# EngineCard.net
KiCad netlist of a schematic drawn in EAGLE
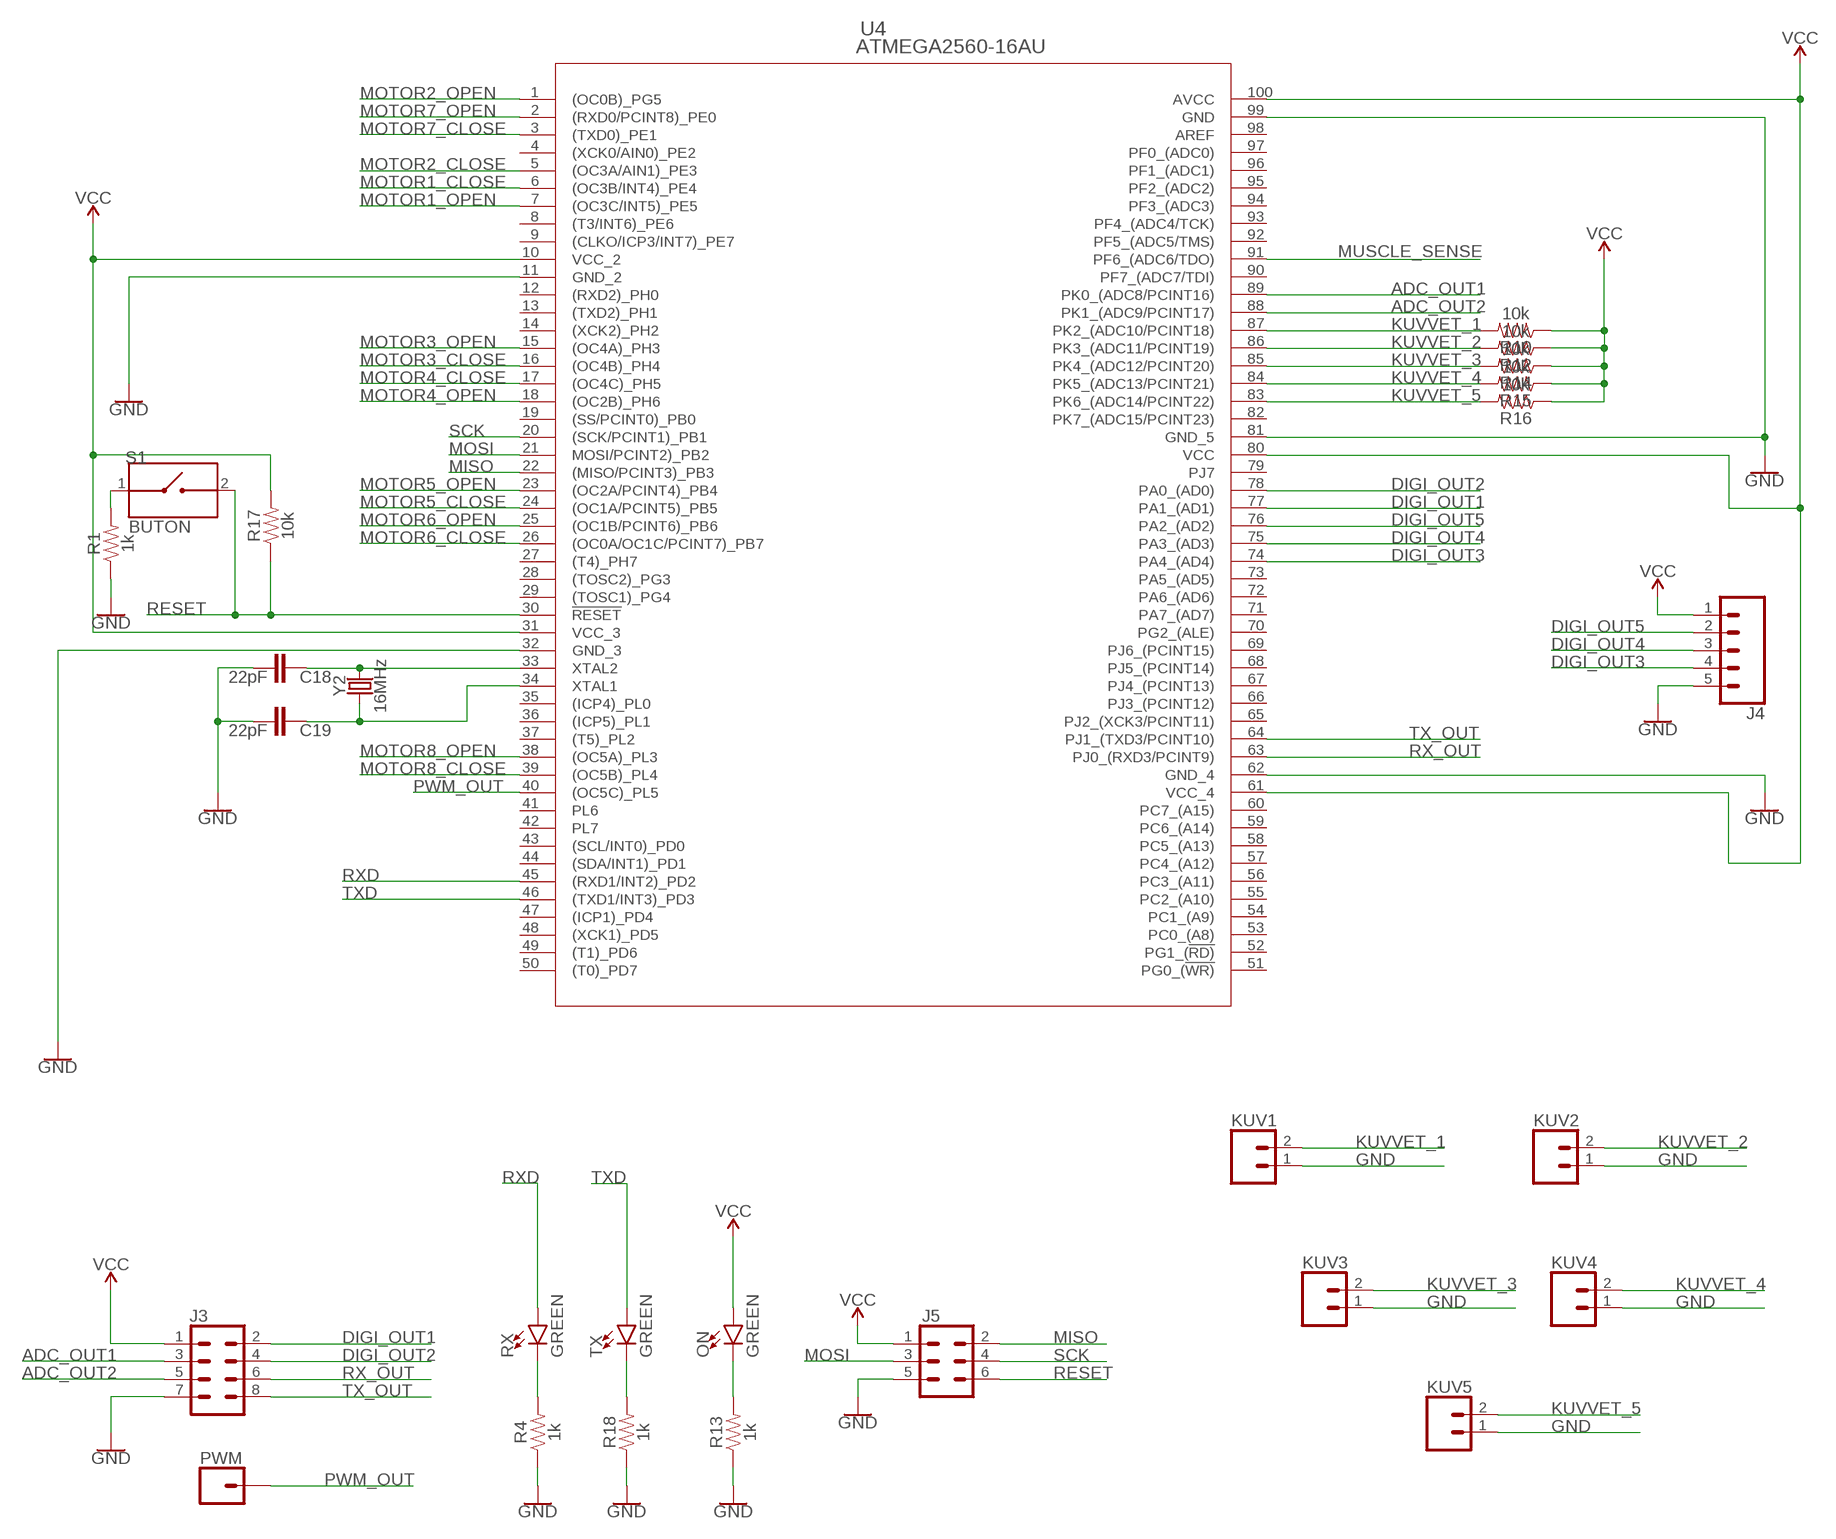
[diagram p0: schematic, sheet 1, part 1 of 2]
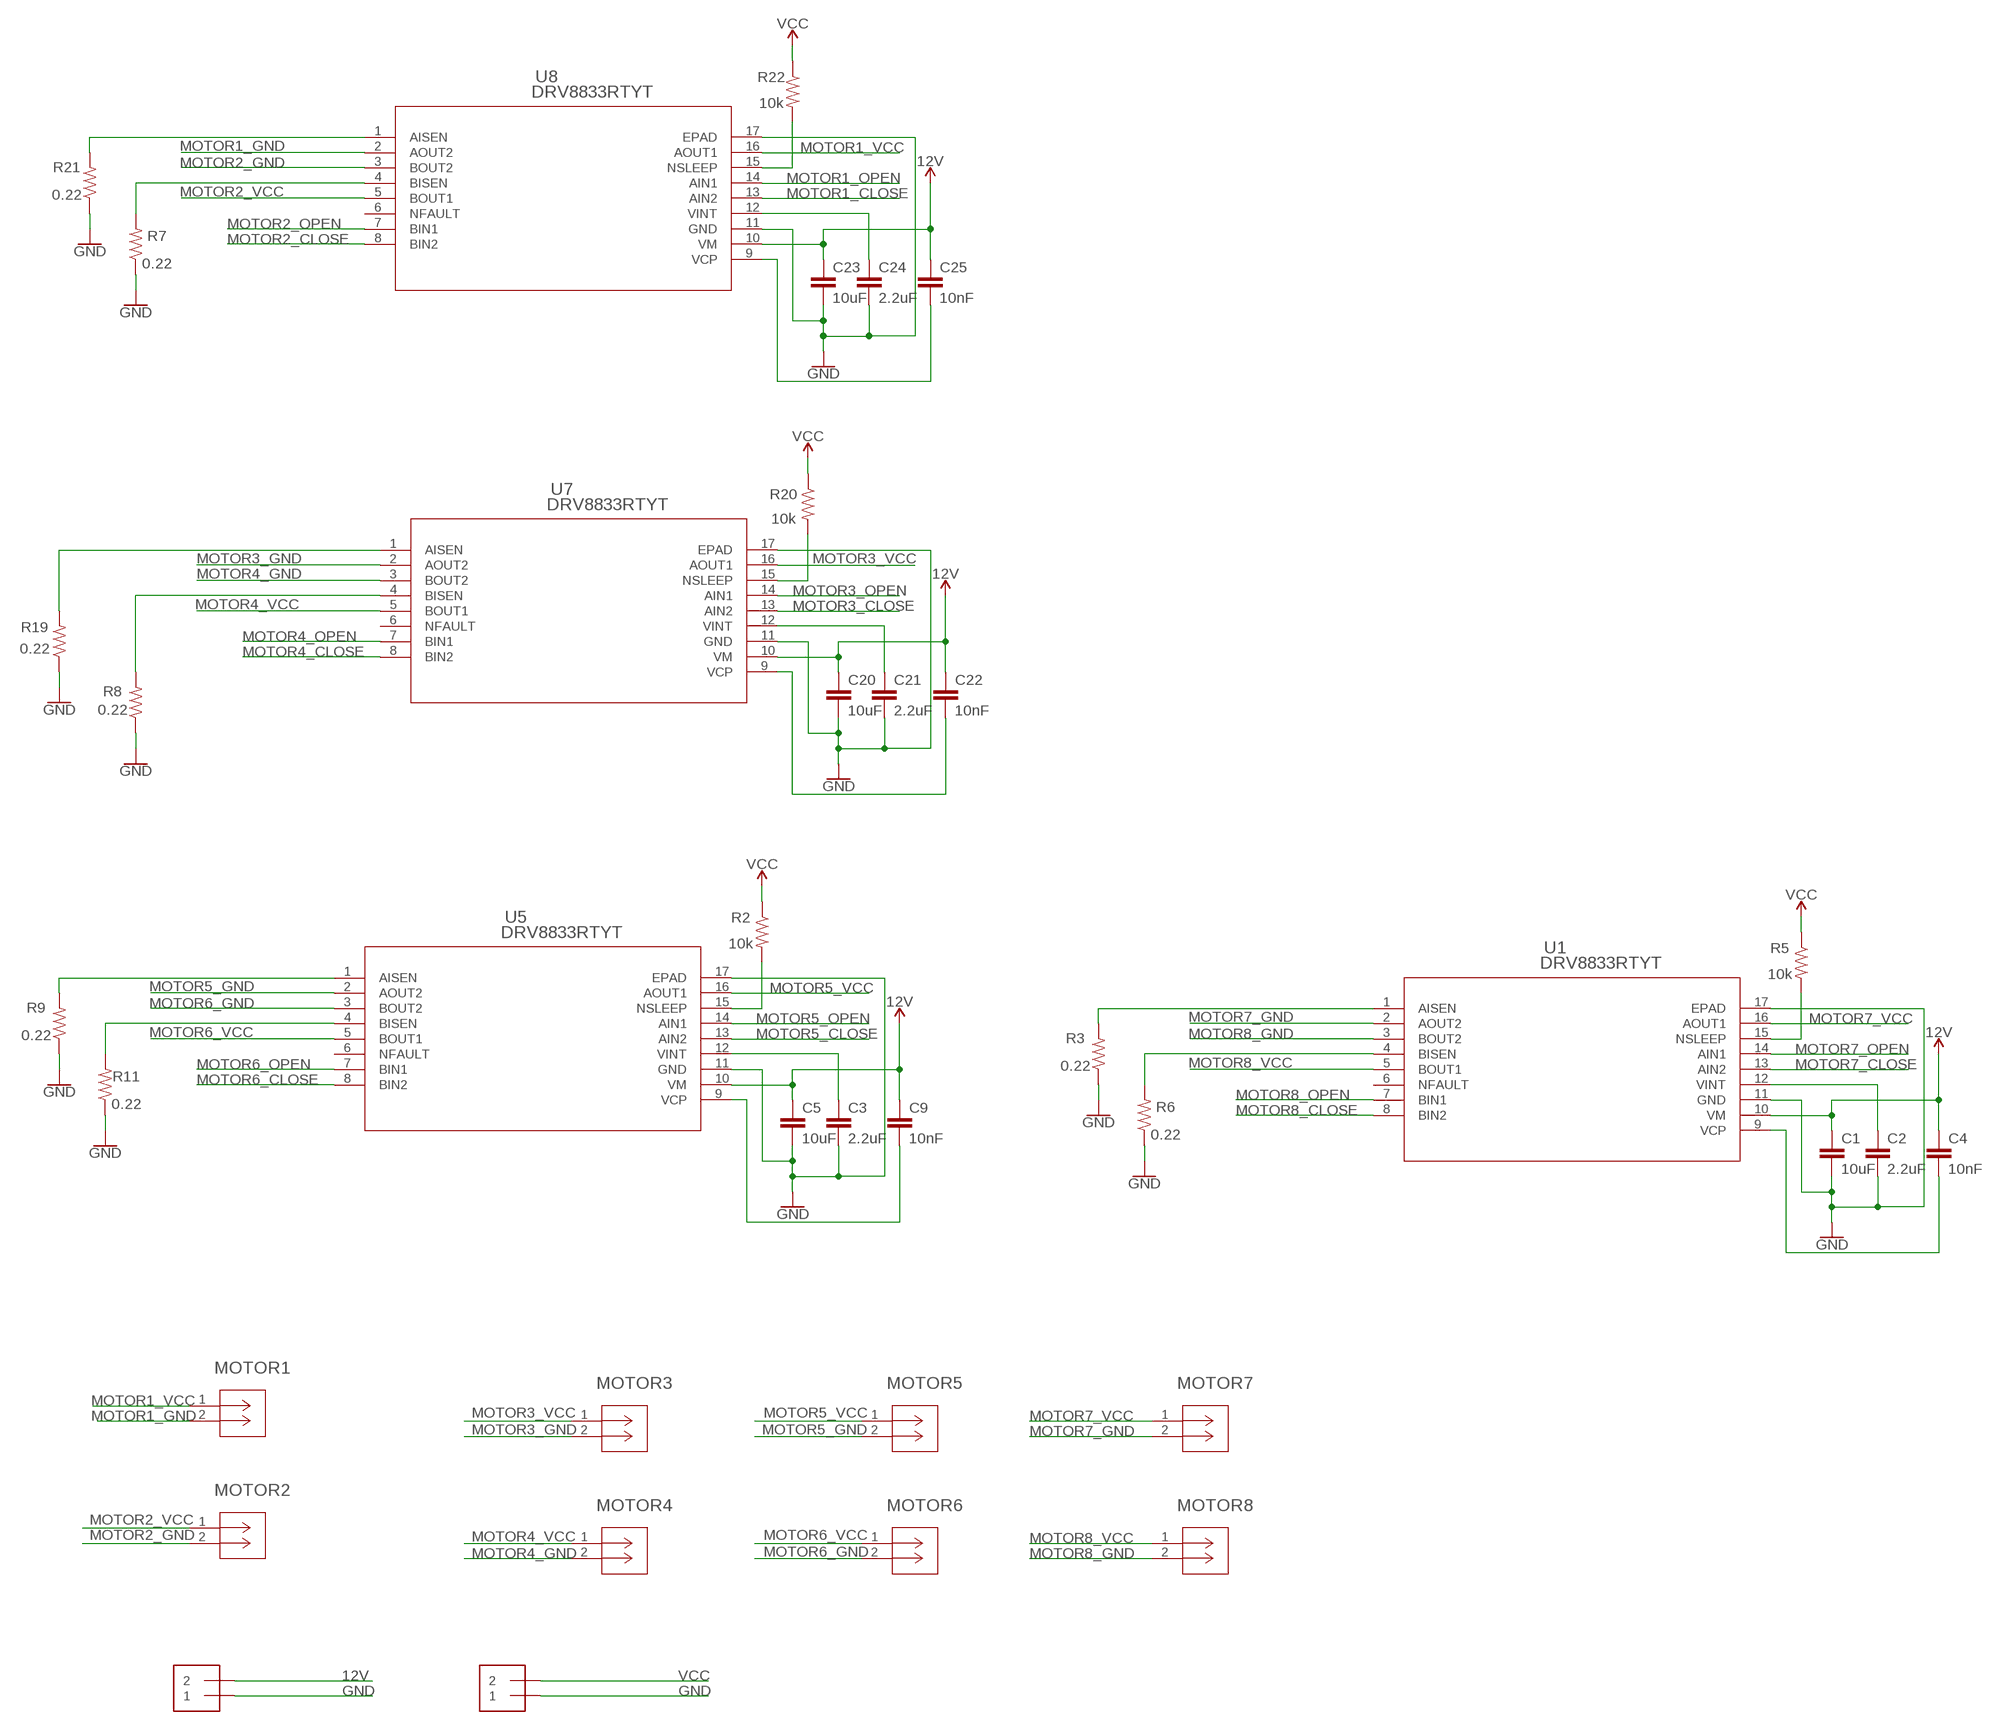
[diagram p1: schematic, sheet 1, part 2 of 2]

(export (version "E")
  (design (tool "Eeschema 10.0.6"))
  (components
    (comp (ref "C1")
      (value "10uF")
      (footprint "eagle-import:0603")
      (libsource (lib "eagle-import") (part "10UF-0603-6.3V-20%"))
    )
    (comp (ref "C2")
      (value "2.2uF")
      (footprint "eagle-import:0603")
      (libsource (lib "eagle-import") (part "2.2UF-0603-10V-20%"))
    )
    (comp (ref "C3")
      (value "2.2uF")
      (footprint "eagle-import:0603")
      (libsource (lib "eagle-import") (part "2.2UF-0603-10V-20%"))
    )
    (comp (ref "C4")
      (value "10nF")
      (footprint "eagle-import:0603")
      (libsource (lib "eagle-import") (part "10NF-0603-50V-10%"))
    )
    (comp (ref "C5")
      (value "10uF")
      (footprint "eagle-import:0603")
      (libsource (lib "eagle-import") (part "10UF-0603-6.3V-20%"))
    )
    (comp (ref "C9")
      (value "10nF")
      (footprint "eagle-import:0603")
      (libsource (lib "eagle-import") (part "10NF-0603-50V-10%"))
    )
    (comp (ref "C18")
      (value "22pF")
      (footprint "eagle-import:0603")
      (libsource (lib "eagle-import") (part "22PF-0603-50V-5%"))
    )
    (comp (ref "C19")
      (value "22pF")
      (footprint "eagle-import:0603")
      (libsource (lib "eagle-import") (part "22PF-0603-50V-5%"))
    )
    (comp (ref "C20")
      (value "10uF")
      (footprint "eagle-import:0603")
      (libsource (lib "eagle-import") (part "10UF-0603-6.3V-20%"))
    )
    (comp (ref "C21")
      (value "2.2uF")
      (footprint "eagle-import:0603")
      (libsource (lib "eagle-import") (part "2.2UF-0603-10V-20%"))
    )
    (comp (ref "C22")
      (value "10nF")
      (footprint "eagle-import:0603")
      (libsource (lib "eagle-import") (part "10NF-0603-50V-10%"))
    )
    (comp (ref "C23")
      (value "10uF")
      (footprint "eagle-import:0603")
      (libsource (lib "eagle-import") (part "10UF-0603-6.3V-20%"))
    )
    (comp (ref "C24")
      (value "2.2uF")
      (footprint "eagle-import:0603")
      (libsource (lib "eagle-import") (part "2.2UF-0603-10V-20%"))
    )
    (comp (ref "C25")
      (value "10nF")
      (footprint "eagle-import:0603")
      (libsource (lib "eagle-import") (part "10NF-0603-50V-10%"))
    )
    (comp (ref "J3")
      (value "CONN_04X2")
      (footprint "eagle-import:2X4")
      (libsource (lib "eagle-import") (part "CONN_04X2"))
    )
    (comp (ref "J4")
      (value "CONN_05NO_SILK")
      (footprint "eagle-import:1X05_NO_SILK")
      (libsource (lib "eagle-import") (part "CONN_05NO_SILK"))
    )
    (comp (ref "J5")
      (value "CONN_03X2NO_SILK")
      (footprint "eagle-import:2X3-NS")
      (libsource (lib "eagle-import") (part "CONN_03X2NO_SILK"))
    )
    (comp (ref "KUV1")
      (value "CONN_02")
      (footprint "eagle-import:1X02")
      (libsource (lib "eagle-import") (part "CONN_02"))
    )
    (comp (ref "KUV2")
      (value "CONN_02")
      (footprint "eagle-import:1X02")
      (libsource (lib "eagle-import") (part "CONN_02"))
    )
    (comp (ref "KUV3")
      (value "CONN_02")
      (footprint "eagle-import:1X02")
      (libsource (lib "eagle-import") (part "CONN_02"))
    )
    (comp (ref "KUV4")
      (value "CONN_02")
      (footprint "eagle-import:1X02")
      (libsource (lib "eagle-import") (part "CONN_02"))
    )
    (comp (ref "KUV5")
      (value "CONN_02")
      (footprint "eagle-import:1X02")
      (libsource (lib "eagle-import") (part "CONN_02"))
    )
    (comp (ref "MOTOR1")
      (value "530470210")
      (footprint "eagle-import:CON_530470210_MOL")
      (fields (field (name "COPYRIGHT") "Copyright (C) 2022 Ultra Librarian. All rights reserved."))
      (libsource (lib "eagle-import") (part "530470210"))
    )
    (comp (ref "MOTOR2")
      (value "530470210")
      (footprint "eagle-import:CON_530470210_MOL")
      (fields (field (name "COPYRIGHT") "Copyright (C) 2022 Ultra Librarian. All rights reserved."))
      (libsource (lib "eagle-import") (part "530470210"))
    )
    (comp (ref "MOTOR3")
      (value "530470210")
      (footprint "eagle-import:CON_530470210_MOL")
      (fields (field (name "COPYRIGHT") "Copyright (C) 2022 Ultra Librarian. All rights reserved."))
      (libsource (lib "eagle-import") (part "530470210"))
    )
    (comp (ref "MOTOR4")
      (value "530470210")
      (footprint "eagle-import:CON_530470210_MOL")
      (fields (field (name "COPYRIGHT") "Copyright (C) 2022 Ultra Librarian. All rights reserved."))
      (libsource (lib "eagle-import") (part "530470210"))
    )
    (comp (ref "MOTOR5")
      (value "530470210")
      (footprint "eagle-import:CON_530470210_MOL")
      (fields (field (name "COPYRIGHT") "Copyright (C) 2022 Ultra Librarian. All rights reserved."))
      (libsource (lib "eagle-import") (part "530470210"))
    )
    (comp (ref "MOTOR6")
      (value "530470210")
      (footprint "eagle-import:CON_530470210_MOL")
      (fields (field (name "COPYRIGHT") "Copyright (C) 2022 Ultra Librarian. All rights reserved."))
      (libsource (lib "eagle-import") (part "530470210"))
    )
    (comp (ref "MOTOR7")
      (value "530470210")
      (footprint "eagle-import:CON_530470210_MOL")
      (fields (field (name "COPYRIGHT") "Copyright (C) 2022 Ultra Librarian. All rights reserved."))
      (libsource (lib "eagle-import") (part "530470210"))
    )
    (comp (ref "MOTOR8")
      (value "530470210")
      (footprint "eagle-import:CON_530470210_MOL")
      (fields (field (name "COPYRIGHT") "Copyright (C) 2022 Ultra Librarian. All rights reserved."))
      (libsource (lib "eagle-import") (part "530470210"))
    )
    (comp (ref "ON")
      (value "GREEN")
      (footprint "eagle-import:LED-0603")
      (libsource (lib "eagle-import") (part "LED-GREEN0603"))
    )
    (comp (ref "PIL")
      (value "1X2-3.5MM")
      (footprint "eagle-import:1X2-3.5MM")
      (libsource (lib "eagle-import") (part "1X2-3.5MM"))
    )
    (comp (ref "PWM")
      (value "CONN_01")
      (footprint "eagle-import:1X01")
      (libsource (lib "eagle-import") (part "CONN_01"))
    )
    (comp (ref "R1")
      (value "1k")
      (footprint "eagle-import:0603")
      (libsource (lib "eagle-import") (part "10KOHM-0603-1/10W-1%"))
    )
    (comp (ref "R2")
      (value "10k")
      (footprint "eagle-import:0603")
      (libsource (lib "eagle-import") (part "10KOHM-0603-1/10W-1%"))
    )
    (comp (ref "R3")
      (value "0.22")
      (footprint "eagle-import:0805")
      (libsource (lib "eagle-import") (part "0.22OHM-0805-1/4W-1%"))
    )
    (comp (ref "R4")
      (value "1k")
      (footprint "eagle-import:0603")
      (libsource (lib "eagle-import") (part "1KOHM-0603-1/10W-1%"))
    )
    (comp (ref "R5")
      (value "10k")
      (footprint "eagle-import:0603")
      (libsource (lib "eagle-import") (part "10KOHM-0603-1/10W-1%"))
    )
    (comp (ref "R6")
      (value "0.22")
      (footprint "eagle-import:0805")
      (libsource (lib "eagle-import") (part "0.22OHM-0805-1/4W-1%"))
    )
    (comp (ref "R7")
      (value "0.22")
      (footprint "eagle-import:0805")
      (libsource (lib "eagle-import") (part "0.22OHM-0805-1/4W-1%"))
    )
    (comp (ref "R8")
      (value "0.22")
      (footprint "eagle-import:0805")
      (libsource (lib "eagle-import") (part "0.22OHM-0805-1/4W-1%"))
    )
    (comp (ref "R9")
      (value "0.22")
      (footprint "eagle-import:0805")
      (libsource (lib "eagle-import") (part "0.22OHM-0805-1/4W-1%"))
    )
    (comp (ref "R10")
      (value "10k")
      (footprint "eagle-import:0603")
      (libsource (lib "eagle-import") (part "10KOHM-0603-1/10W-1%"))
    )
    (comp (ref "R11")
      (value "0.22")
      (footprint "eagle-import:0805")
      (libsource (lib "eagle-import") (part "0.22OHM-0805-1/4W-1%"))
    )
    (comp (ref "R12")
      (value "10k")
      (footprint "eagle-import:0603")
      (libsource (lib "eagle-import") (part "10KOHM-0603-1/10W-1%"))
    )
    (comp (ref "R13")
      (value "1k")
      (footprint "eagle-import:0603")
      (libsource (lib "eagle-import") (part "1KOHM-0603-1/10W-1%"))
    )
    (comp (ref "R14")
      (value "10k")
      (footprint "eagle-import:0603")
      (libsource (lib "eagle-import") (part "10KOHM-0603-1/10W-1%"))
    )
    (comp (ref "R15")
      (value "10k")
      (footprint "eagle-import:0603")
      (libsource (lib "eagle-import") (part "10KOHM-0603-1/10W-1%"))
    )
    (comp (ref "R16")
      (value "10k")
      (footprint "eagle-import:0603")
      (libsource (lib "eagle-import") (part "10KOHM-0603-1/10W-1%"))
    )
    (comp (ref "R17")
      (value "10k")
      (footprint "eagle-import:0603")
      (libsource (lib "eagle-import") (part "10KOHM-0603-1/10W-1%"))
    )
    (comp (ref "R18")
      (value "1k")
      (footprint "eagle-import:0603")
      (libsource (lib "eagle-import") (part "1KOHM-0603-1/10W-1%"))
    )
    (comp (ref "R19")
      (value "0.22")
      (footprint "eagle-import:0805")
      (libsource (lib "eagle-import") (part "0.22OHM-0805-1/4W-1%"))
    )
    (comp (ref "R20")
      (value "10k")
      (footprint "eagle-import:0603")
      (libsource (lib "eagle-import") (part "10KOHM-0603-1/10W-1%"))
    )
    (comp (ref "R21")
      (value "0.22")
      (footprint "eagle-import:0805")
      (libsource (lib "eagle-import") (part "0.22OHM-0805-1/4W-1%"))
    )
    (comp (ref "R22")
      (value "10k")
      (footprint "eagle-import:0603")
      (libsource (lib "eagle-import") (part "10KOHM-0603-1/10W-1%"))
    )
    (comp (ref "REG")
      (value "1X2-3.5MM")
      (footprint "eagle-import:1X2-3.5MM")
      (libsource (lib "eagle-import") (part "1X2-3.5MM"))
    )
    (comp (ref "RX")
      (value "GREEN")
      (footprint "eagle-import:LED-0603")
      (libsource (lib "eagle-import") (part "LED-GREEN0603"))
    )
    (comp (ref "S1")
      (value "BUTON")
      (footprint "eagle-import:SW_1437566-4")
      (fields
        (field (name "COMMENT") "1437566-4")
        (field (name "MF") "TE Connectivity")
        (field (name "MP") "FSMSMTR")
      )
      (libsource (lib "eagle-import") (part "1437566-4"))
    )
    (comp (ref "TX")
      (value "GREEN")
      (footprint "eagle-import:LED-0603")
      (libsource (lib "eagle-import") (part "LED-GREEN0603"))
    )
    (comp (ref "U1")
      (value "DRV8833RTYT")
      (footprint "eagle-import:RTY16")
      (fields
        (field (name "GENERIC_PART_NUMBER") "DRV8833")
        (field (name "MANUFACTURER") "Texas Instruments")
      )
      (libsource (lib "eagle-import") (part "DRV8833RTYT"))
    )
    (comp (ref "U4")
      (value "ATMEGA2560-16AU")
      (footprint "eagle-import:100A_ATM")
      (libsource (lib "eagle-import") (part "ATMEGA2560-16AU"))
    )
    (comp (ref "U5")
      (value "DRV8833RTYT")
      (footprint "eagle-import:RTY16")
      (fields
        (field (name "GENERIC_PART_NUMBER") "DRV8833")
        (field (name "MANUFACTURER") "Texas Instruments")
      )
      (libsource (lib "eagle-import") (part "DRV8833RTYT"))
    )
    (comp (ref "U7")
      (value "DRV8833RTYT")
      (footprint "eagle-import:RTY16")
      (fields
        (field (name "GENERIC_PART_NUMBER") "DRV8833")
        (field (name "MANUFACTURER") "Texas Instruments")
      )
      (libsource (lib "eagle-import") (part "DRV8833RTYT"))
    )
    (comp (ref "U8")
      (value "DRV8833RTYT")
      (footprint "eagle-import:RTY16")
      (fields
        (field (name "GENERIC_PART_NUMBER") "DRV8833")
        (field (name "MANUFACTURER") "Texas Instruments")
      )
      (libsource (lib "eagle-import") (part "DRV8833RTYT"))
    )
    (comp (ref "Y2")
      (value "16MHz")
      (footprint "eagle-import:HC49US")
      (libsource (lib "eagle-import") (part "CRYSTAL-16MHZPTH-HC49US"))
    )
  )
  (nets
    (net (code "1") (name "/ADC_OUT1") (class "Default")
      (node (ref "J3") (pin "3") (pinfunction "3_3") (pintype "passive"))
      (node (ref "U4") (pin "89") (pinfunction "PK0_(ADC8/PCINT16)_89") (pintype "bidirectional"))
    )
    (net (code "2") (name "/ADC_OUT2") (class "Default")
      (node (ref "J3") (pin "5") (pinfunction "5_5") (pintype "passive"))
      (node (ref "U4") (pin "88") (pinfunction "PK1_(ADC9/PCINT17)_88") (pintype "bidirectional"))
    )
    (net (code "3") (name "/AREF") (class "Default")
      (node (ref "U4") (pin "98") (pinfunction "AREF_98") (pintype "power_in"))
    )
    (net (code "4") (name "/DIGI_OUT1") (class "Default")
      (node (ref "J3") (pin "2") (pinfunction "2_2") (pintype "passive"))
      (node (ref "U4") (pin "77") (pinfunction "PA1_(AD1)_77") (pintype "bidirectional"))
    )
    (net (code "5") (name "/DIGI_OUT2") (class "Default")
      (node (ref "J3") (pin "4") (pinfunction "4_4") (pintype "passive"))
      (node (ref "U4") (pin "78") (pinfunction "PA0_(AD0)_78") (pintype "bidirectional"))
    )
    (net (code "6") (name "/DIGI_OUT3") (class "Default")
      (node (ref "J4") (pin "4") (pinfunction "4_4") (pintype "passive"))
      (node (ref "U4") (pin "74") (pinfunction "PA4_(AD4)_74") (pintype "bidirectional"))
    )
    (net (code "7") (name "/DIGI_OUT4") (class "Default")
      (node (ref "J4") (pin "3") (pinfunction "3_3") (pintype "passive"))
      (node (ref "U4") (pin "75") (pinfunction "PA3_(AD3)_75") (pintype "bidirectional"))
    )
    (net (code "8") (name "/DIGI_OUT5") (class "Default")
      (node (ref "J4") (pin "2") (pinfunction "2_2") (pintype "passive"))
      (node (ref "U4") (pin "76") (pinfunction "PA2_(AD2)_76") (pintype "bidirectional"))
    )
    (net (code "9") (name "/KUVVET_1") (class "Default")
      (node (ref "KUV1") (pin "2") (pinfunction "2_2") (pintype "passive"))
      (node (ref "R10") (pin "2") (pinfunction "2_2") (pintype "passive"))
      (node (ref "U4") (pin "87") (pinfunction "PK2_(ADC10/PCINT18)_87") (pintype "bidirectional"))
    )
    (net (code "10") (name "/KUVVET_2") (class "Default")
      (node (ref "KUV2") (pin "2") (pinfunction "2_2") (pintype "passive"))
      (node (ref "R12") (pin "2") (pinfunction "2_2") (pintype "passive"))
      (node (ref "U4") (pin "86") (pinfunction "PK3_(ADC11/PCINT19)_86") (pintype "bidirectional"))
    )
    (net (code "11") (name "/KUVVET_3") (class "Default")
      (node (ref "KUV3") (pin "2") (pinfunction "2_2") (pintype "passive"))
      (node (ref "R14") (pin "2") (pinfunction "2_2") (pintype "passive"))
      (node (ref "U4") (pin "85") (pinfunction "PK4_(ADC12/PCINT20)_85") (pintype "bidirectional"))
    )
    (net (code "12") (name "/KUVVET_4") (class "Default")
      (node (ref "KUV4") (pin "2") (pinfunction "2_2") (pintype "passive"))
      (node (ref "R15") (pin "2") (pinfunction "2_2") (pintype "passive"))
      (node (ref "U4") (pin "84") (pinfunction "PK5_(ADC13/PCINT21)_84") (pintype "bidirectional"))
    )
    (net (code "13") (name "/KUVVET_5") (class "Default")
      (node (ref "KUV5") (pin "2") (pinfunction "2_2") (pintype "passive"))
      (node (ref "R16") (pin "2") (pinfunction "2_2") (pintype "passive"))
      (node (ref "U4") (pin "83") (pinfunction "PK6_(ADC14/PCINT22)_83") (pintype "bidirectional"))
    )
    (net (code "14") (name "/MISO") (class "Default")
      (node (ref "J5") (pin "2") (pinfunction "2_2") (pintype "bidirectional"))
      (node (ref "U4") (pin "22") (pinfunction "(MISO/PCINT3)_PB3_22") (pintype "bidirectional"))
    )
    (net (code "15") (name "/MOSI") (class "Default")
      (node (ref "J5") (pin "3") (pinfunction "3_3") (pintype "bidirectional"))
      (node (ref "U4") (pin "21") (pinfunction "MOSI/PCINT2)_PB2_21") (pintype "bidirectional"))
    )
    (net (code "16") (name "/MOTOR1_CLOSE") (class "Default")
      (node (ref "U4") (pin "6") (pinfunction "(OC3B/INT4)_PE4_6") (pintype "bidirectional"))
      (node (ref "U8") (pin "13") (pinfunction "AIN2_13") (pintype "input"))
    )
    (net (code "17") (name "/MOTOR1_GND") (class "Default")
      (node (ref "MOTOR1") (pin "2") (pinfunction "2_2") (pintype "passive"))
      (node (ref "U8") (pin "2") (pinfunction "AOUT2_2") (pintype "output"))
    )
    (net (code "18") (name "/MOTOR1_OPEN") (class "Default")
      (node (ref "U4") (pin "7") (pinfunction "(OC3C/INT5)_PE5_7") (pintype "bidirectional"))
      (node (ref "U8") (pin "14") (pinfunction "AIN1_14") (pintype "input"))
    )
    (net (code "19") (name "/MOTOR1_VCC") (class "Default")
      (node (ref "MOTOR1") (pin "1") (pinfunction "1_1") (pintype "passive"))
      (node (ref "U8") (pin "16") (pinfunction "AOUT1_16") (pintype "output"))
    )
    (net (code "20") (name "/MOTOR2_CLOSE") (class "Default")
      (node (ref "U4") (pin "5") (pinfunction "(OC3A/AIN1)_PE3_5") (pintype "bidirectional"))
      (node (ref "U8") (pin "8") (pinfunction "BIN2_8") (pintype "input"))
    )
    (net (code "21") (name "/MOTOR2_GND") (class "Default")
      (node (ref "MOTOR2") (pin "2") (pinfunction "2_2") (pintype "passive"))
      (node (ref "U8") (pin "3") (pinfunction "BOUT2_3") (pintype "output"))
    )
    (net (code "22") (name "/MOTOR2_OPEN") (class "Default")
      (node (ref "U4") (pin "1") (pinfunction "(OC0B)_PG5_1") (pintype "bidirectional"))
      (node (ref "U8") (pin "7") (pinfunction "BIN1_7") (pintype "input"))
    )
    (net (code "23") (name "/MOTOR2_VCC") (class "Default")
      (node (ref "MOTOR2") (pin "1") (pinfunction "1_1") (pintype "passive"))
      (node (ref "U8") (pin "5") (pinfunction "BOUT1_5") (pintype "output"))
    )
    (net (code "24") (name "/MOTOR3_CLOSE") (class "Default")
      (node (ref "U4") (pin "16") (pinfunction "(OC4B)_PH4_16") (pintype "bidirectional"))
      (node (ref "U7") (pin "13") (pinfunction "AIN2_13") (pintype "input"))
    )
    (net (code "25") (name "/MOTOR3_GND") (class "Default")
      (node (ref "MOTOR3") (pin "2") (pinfunction "2_2") (pintype "passive"))
      (node (ref "U7") (pin "2") (pinfunction "AOUT2_2") (pintype "output"))
    )
    (net (code "26") (name "/MOTOR3_OPEN") (class "Default")
      (node (ref "U4") (pin "15") (pinfunction "(OC4A)_PH3_15") (pintype "bidirectional"))
      (node (ref "U7") (pin "14") (pinfunction "AIN1_14") (pintype "input"))
    )
    (net (code "27") (name "/MOTOR3_VCC") (class "Default")
      (node (ref "MOTOR3") (pin "1") (pinfunction "1_1") (pintype "passive"))
      (node (ref "U7") (pin "16") (pinfunction "AOUT1_16") (pintype "output"))
    )
    (net (code "28") (name "/MOTOR4_CLOSE") (class "Default")
      (node (ref "U4") (pin "17") (pinfunction "(OC4C)_PH5_17") (pintype "bidirectional"))
      (node (ref "U7") (pin "8") (pinfunction "BIN2_8") (pintype "input"))
    )
    (net (code "29") (name "/MOTOR4_GND") (class "Default")
      (node (ref "MOTOR4") (pin "2") (pinfunction "2_2") (pintype "passive"))
      (node (ref "U7") (pin "3") (pinfunction "BOUT2_3") (pintype "output"))
    )
    (net (code "30") (name "/MOTOR4_OPEN") (class "Default")
      (node (ref "U4") (pin "18") (pinfunction "(OC2B)_PH6_18") (pintype "bidirectional"))
      (node (ref "U7") (pin "7") (pinfunction "BIN1_7") (pintype "input"))
    )
    (net (code "31") (name "/MOTOR4_VCC") (class "Default")
      (node (ref "MOTOR4") (pin "1") (pinfunction "1_1") (pintype "passive"))
      (node (ref "U7") (pin "5") (pinfunction "BOUT1_5") (pintype "output"))
    )
    (net (code "32") (name "/MOTOR5_CLOSE") (class "Default")
      (node (ref "U4") (pin "24") (pinfunction "(OC1A/PCINT5)_PB5_24") (pintype "bidirectional"))
      (node (ref "U5") (pin "13") (pinfunction "AIN2_13") (pintype "input"))
    )
    (net (code "33") (name "/MOTOR5_GND") (class "Default")
      (node (ref "MOTOR5") (pin "2") (pinfunction "2_2") (pintype "passive"))
      (node (ref "U5") (pin "2") (pinfunction "AOUT2_2") (pintype "output"))
    )
    (net (code "34") (name "/MOTOR5_OPEN") (class "Default")
      (node (ref "U4") (pin "23") (pinfunction "(OC2A/PCINT4)_PB4_23") (pintype "bidirectional"))
      (node (ref "U5") (pin "14") (pinfunction "AIN1_14") (pintype "input"))
    )
    (net (code "35") (name "/MOTOR5_VCC") (class "Default")
      (node (ref "MOTOR5") (pin "1") (pinfunction "1_1") (pintype "passive"))
      (node (ref "U5") (pin "16") (pinfunction "AOUT1_16") (pintype "output"))
    )
    (net (code "36") (name "/MOTOR6_CLOSE") (class "Default")
      (node (ref "U4") (pin "26") (pinfunction "(OC0A/OC1C/PCINT7)_PB7_26") (pintype "bidirectional"))
      (node (ref "U5") (pin "8") (pinfunction "BIN2_8") (pintype "input"))
    )
    (net (code "37") (name "/MOTOR6_GND") (class "Default")
      (node (ref "MOTOR6") (pin "2") (pinfunction "2_2") (pintype "passive"))
      (node (ref "U5") (pin "3") (pinfunction "BOUT2_3") (pintype "output"))
    )
    (net (code "38") (name "/MOTOR6_OPEN") (class "Default")
      (node (ref "U4") (pin "25") (pinfunction "(OC1B/PCINT6)_PB6_25") (pintype "bidirectional"))
      (node (ref "U5") (pin "7") (pinfunction "BIN1_7") (pintype "input"))
    )
    (net (code "39") (name "/MOTOR6_VCC") (class "Default")
      (node (ref "MOTOR6") (pin "1") (pinfunction "1_1") (pintype "passive"))
      (node (ref "U5") (pin "5") (pinfunction "BOUT1_5") (pintype "output"))
    )
    (net (code "40") (name "/MOTOR7_CLOSE") (class "Default")
      (node (ref "U1") (pin "13") (pinfunction "AIN2_13") (pintype "input"))
      (node (ref "U4") (pin "3") (pinfunction "(TXD0)_PE1_3") (pintype "bidirectional"))
    )
    (net (code "41") (name "/MOTOR7_GND") (class "Default")
      (node (ref "MOTOR7") (pin "2") (pinfunction "2_2") (pintype "passive"))
      (node (ref "U1") (pin "2") (pinfunction "AOUT2_2") (pintype "output"))
    )
    (net (code "42") (name "/MOTOR7_OPEN") (class "Default")
      (node (ref "U1") (pin "14") (pinfunction "AIN1_14") (pintype "input"))
      (node (ref "U4") (pin "2") (pinfunction "(RXD0/PCINT8)_PE0_2") (pintype "bidirectional"))
    )
    (net (code "43") (name "/MOTOR7_VCC") (class "Default")
      (node (ref "MOTOR7") (pin "1") (pinfunction "1_1") (pintype "passive"))
      (node (ref "U1") (pin "16") (pinfunction "AOUT1_16") (pintype "output"))
    )
    (net (code "44") (name "/MOTOR8_CLOSE") (class "Default")
      (node (ref "U1") (pin "8") (pinfunction "BIN2_8") (pintype "input"))
      (node (ref "U4") (pin "39") (pinfunction "(OC5B)_PL4_39") (pintype "bidirectional"))
    )
    (net (code "45") (name "/MOTOR8_GND") (class "Default")
      (node (ref "MOTOR8") (pin "2") (pinfunction "2_2") (pintype "passive"))
      (node (ref "U1") (pin "3") (pinfunction "BOUT2_3") (pintype "output"))
    )
    (net (code "46") (name "/MOTOR8_OPEN") (class "Default")
      (node (ref "U1") (pin "7") (pinfunction "BIN1_7") (pintype "input"))
      (node (ref "U4") (pin "38") (pinfunction "(OC5A)_PL3_38") (pintype "bidirectional"))
    )
    (net (code "47") (name "/MOTOR8_VCC") (class "Default")
      (node (ref "MOTOR8") (pin "1") (pinfunction "1_1") (pintype "passive"))
      (node (ref "U1") (pin "5") (pinfunction "BOUT1_5") (pintype "output"))
    )
    (net (code "48") (name "/MUSCLE_SENSE") (class "Default")
      (node (ref "U4") (pin "91") (pinfunction "PF6_(ADC6/TDO)_91") (pintype "bidirectional"))
    )
    (net (code "49") (name "/PWM_OUT") (class "Default")
      (node (ref "PWM") (pin "1") (pinfunction "1_1") (pintype "passive"))
      (node (ref "U4") (pin "40") (pinfunction "(OC5C)_PL5_40") (pintype "bidirectional"))
    )
    (net (code "50") (name "/RESET") (class "Default")
      (node (ref "J5") (pin "6") (pinfunction "6_6") (pintype "bidirectional"))
      (node (ref "R17") (pin "1") (pinfunction "1_1") (pintype "passive"))
      (node (ref "S1") (pin "2") (pinfunction "2_2") (pintype "passive"))
      (node (ref "U4") (pin "30") (pinfunction "~{RESET}_30") (pintype "input"))
    )
    (net (code "51") (name "/RXD") (class "Default")
      (node (ref "RX") (pin "A") (pinfunction "A_A") (pintype "passive"))
      (node (ref "U4") (pin "45") (pinfunction "(RXD1/INT2)_PD2_45") (pintype "bidirectional"))
    )
    (net (code "52") (name "/RX_OUT") (class "Default")
      (node (ref "J3") (pin "6") (pinfunction "6_6") (pintype "passive"))
      (node (ref "U4") (pin "63") (pinfunction "PJ0_(RXD3/PCINT9)_63") (pintype "bidirectional"))
    )
    (net (code "53") (name "/SCK") (class "Default")
      (node (ref "J5") (pin "4") (pinfunction "4_4") (pintype "bidirectional"))
      (node (ref "U4") (pin "20") (pinfunction "(SCK/PCINT1)_PB1_20") (pintype "bidirectional"))
    )
    (net (code "54") (name "/TXD") (class "Default")
      (node (ref "TX") (pin "A") (pinfunction "A_A") (pintype "passive"))
      (node (ref "U4") (pin "46") (pinfunction "(TXD1/INT3)_PD3_46") (pintype "bidirectional"))
    )
    (net (code "55") (name "/TX_OUT") (class "Default")
      (node (ref "J3") (pin "8") (pinfunction "8_8") (pintype "passive"))
      (node (ref "U4") (pin "64") (pinfunction "PJ1_(TXD3/PCINT10)_64") (pintype "bidirectional"))
    )
    (net (code "56") (name "12V") (class "Default")
      (node (ref "C1") (pin "1") (pinfunction "1_1") (pintype "passive"))
      (node (ref "C20") (pin "1") (pinfunction "1_1") (pintype "passive"))
      (node (ref "C22") (pin "1") (pinfunction "1_1") (pintype "passive"))
      (node (ref "C23") (pin "1") (pinfunction "1_1") (pintype "passive"))
      (node (ref "C25") (pin "1") (pinfunction "1_1") (pintype "passive"))
      (node (ref "C4") (pin "1") (pinfunction "1_1") (pintype "passive"))
      (node (ref "C5") (pin "1") (pinfunction "1_1") (pintype "passive"))
      (node (ref "C9") (pin "1") (pinfunction "1_1") (pintype "passive"))
      (node (ref "PIL") (pin "2") (pinfunction "2_2") (pintype "passive"))
      (node (ref "U1") (pin "10") (pinfunction "VM_10") (pintype "power_in"))
      (node (ref "U5") (pin "10") (pinfunction "VM_10") (pintype "power_in"))
      (node (ref "U7") (pin "10") (pinfunction "VM_10") (pintype "power_in"))
      (node (ref "U8") (pin "10") (pinfunction "VM_10") (pintype "power_in"))
    )
    (net (code "57") (name "GND") (class "Default")
      (node (ref "C1") (pin "2") (pinfunction "2_2") (pintype "passive"))
      (node (ref "C18") (pin "2") (pinfunction "2_2") (pintype "passive"))
      (node (ref "C19") (pin "2") (pinfunction "2_2") (pintype "passive"))
      (node (ref "C2") (pin "2") (pinfunction "2_2") (pintype "passive"))
      (node (ref "C20") (pin "2") (pinfunction "2_2") (pintype "passive"))
      (node (ref "C21") (pin "2") (pinfunction "2_2") (pintype "passive"))
      (node (ref "C23") (pin "2") (pinfunction "2_2") (pintype "passive"))
      (node (ref "C24") (pin "2") (pinfunction "2_2") (pintype "passive"))
      (node (ref "C3") (pin "2") (pinfunction "2_2") (pintype "passive"))
      (node (ref "C5") (pin "2") (pinfunction "2_2") (pintype "passive"))
      (node (ref "J3") (pin "7") (pinfunction "7_7") (pintype "passive"))
      (node (ref "J4") (pin "5") (pinfunction "5_5") (pintype "passive"))
      (node (ref "J5") (pin "5") (pinfunction "5_5") (pintype "bidirectional"))
      (node (ref "KUV1") (pin "1") (pinfunction "1_1") (pintype "passive"))
      (node (ref "KUV2") (pin "1") (pinfunction "1_1") (pintype "passive"))
      (node (ref "KUV3") (pin "1") (pinfunction "1_1") (pintype "passive"))
      (node (ref "KUV4") (pin "1") (pinfunction "1_1") (pintype "passive"))
      (node (ref "KUV5") (pin "1") (pinfunction "1_1") (pintype "passive"))
      (node (ref "PIL") (pin "1") (pinfunction "1_1") (pintype "passive"))
      (node (ref "R1") (pin "1") (pinfunction "1_1") (pintype "passive"))
      (node (ref "R11") (pin "1") (pinfunction "1_1") (pintype "passive"))
      (node (ref "R13") (pin "1") (pinfunction "1_1") (pintype "passive"))
      (node (ref "R18") (pin "1") (pinfunction "1_1") (pintype "passive"))
      (node (ref "R19") (pin "1") (pinfunction "1_1") (pintype "passive"))
      (node (ref "R21") (pin "1") (pinfunction "1_1") (pintype "passive"))
      (node (ref "R3") (pin "1") (pinfunction "1_1") (pintype "passive"))
      (node (ref "R4") (pin "1") (pinfunction "1_1") (pintype "passive"))
      (node (ref "R6") (pin "1") (pinfunction "1_1") (pintype "passive"))
      (node (ref "R7") (pin "1") (pinfunction "1_1") (pintype "passive"))
      (node (ref "R8") (pin "1") (pinfunction "1_1") (pintype "passive"))
      (node (ref "R9") (pin "1") (pinfunction "1_1") (pintype "passive"))
      (node (ref "REG") (pin "1") (pinfunction "1_1") (pintype "passive"))
      (node (ref "U1") (pin "11") (pinfunction "GND_11") (pintype "power_in"))
      (node (ref "U1") (pin "17") (pinfunction "EPAD_17") (pintype "passive"))
      (node (ref "U4") (pin "11") (pinfunction "GND_2_11") (pintype "power_in"))
      (node (ref "U4") (pin "32") (pinfunction "GND_3_32") (pintype "power_in"))
      (node (ref "U4") (pin "62") (pinfunction "GND_4_62") (pintype "power_in"))
      (node (ref "U4") (pin "81") (pinfunction "GND_5_81") (pintype "power_in"))
      (node (ref "U4") (pin "99") (pinfunction "GND_99") (pintype "passive"))
      (node (ref "U5") (pin "11") (pinfunction "GND_11") (pintype "power_in"))
      (node (ref "U5") (pin "17") (pinfunction "EPAD_17") (pintype "passive"))
      (node (ref "U7") (pin "11") (pinfunction "GND_11") (pintype "power_in"))
      (node (ref "U7") (pin "17") (pinfunction "EPAD_17") (pintype "passive"))
      (node (ref "U8") (pin "11") (pinfunction "GND_11") (pintype "power_in"))
      (node (ref "U8") (pin "17") (pinfunction "EPAD_17") (pintype "passive"))
    )
    (net (code "58") (name "Net-(ON-PadC)") (class "Default")
      (node (ref "ON") (pin "C") (pinfunction "C_C") (pintype "passive"))
      (node (ref "R13") (pin "2") (pinfunction "2_2") (pintype "passive"))
    )
    (net (code "59") (name "Net-(R1-Pad2)") (class "Default")
      (node (ref "R1") (pin "2") (pinfunction "2_2") (pintype "passive"))
      (node (ref "S1") (pin "1") (pinfunction "1_1") (pintype "passive"))
    )
    (net (code "60") (name "Net-(R4-Pad2)") (class "Default")
      (node (ref "R4") (pin "2") (pinfunction "2_2") (pintype "passive"))
      (node (ref "RX") (pin "C") (pinfunction "C_C") (pintype "passive"))
    )
    (net (code "61") (name "Net-(R18-Pad2)") (class "Default")
      (node (ref "R18") (pin "2") (pinfunction "2_2") (pintype "passive"))
      (node (ref "TX") (pin "C") (pinfunction "C_C") (pintype "passive"))
    )
    (net (code "62") (name "Net-(U1-AISEN)") (class "Default")
      (node (ref "R3") (pin "2") (pinfunction "2_2") (pintype "passive"))
      (node (ref "U1") (pin "1") (pinfunction "AISEN_1") (pintype "bidirectional"))
    )
    (net (code "63") (name "Net-(U1-BISEN)") (class "Default")
      (node (ref "R6") (pin "2") (pinfunction "2_2") (pintype "passive"))
      (node (ref "U1") (pin "4") (pinfunction "BISEN_4") (pintype "bidirectional"))
    )
    (net (code "64") (name "Net-(U1-NSLEEP)") (class "Default")
      (node (ref "R5") (pin "2") (pinfunction "2_2") (pintype "passive"))
      (node (ref "U1") (pin "15") (pinfunction "NSLEEP_15") (pintype "input"))
    )
    (net (code "65") (name "Net-(U1-VCP)") (class "Default")
      (node (ref "C4") (pin "2") (pinfunction "2_2") (pintype "passive"))
      (node (ref "U1") (pin "9") (pinfunction "VCP_9") (pintype "bidirectional"))
    )
    (net (code "66") (name "Net-(U1-VINT)") (class "Default")
      (node (ref "C2") (pin "1") (pinfunction "1_1") (pintype "passive"))
      (node (ref "U1") (pin "12") (pinfunction "VINT_12") (pintype "power_in"))
    )
    (net (code "67") (name "Net-(U4-XTAL1)") (class "Default")
      (node (ref "C19") (pin "1") (pinfunction "1_1") (pintype "passive"))
      (node (ref "U4") (pin "34") (pinfunction "XTAL1_34") (pintype "input"))
      (node (ref "Y2") (pin "1") (pinfunction "1_1") (pintype "passive"))
    )
    (net (code "68") (name "Net-(U4-XTAL2)") (class "Default")
      (node (ref "C18") (pin "1") (pinfunction "1_1") (pintype "passive"))
      (node (ref "U4") (pin "33") (pinfunction "XTAL2_33") (pintype "output"))
      (node (ref "Y2") (pin "2") (pinfunction "2_2") (pintype "passive"))
    )
    (net (code "69") (name "Net-(U5-AISEN)") (class "Default")
      (node (ref "R9") (pin "2") (pinfunction "2_2") (pintype "passive"))
      (node (ref "U5") (pin "1") (pinfunction "AISEN_1") (pintype "bidirectional"))
    )
    (net (code "70") (name "Net-(U5-BISEN)") (class "Default")
      (node (ref "R11") (pin "2") (pinfunction "2_2") (pintype "passive"))
      (node (ref "U5") (pin "4") (pinfunction "BISEN_4") (pintype "bidirectional"))
    )
    (net (code "71") (name "Net-(U5-NSLEEP)") (class "Default")
      (node (ref "R2") (pin "2") (pinfunction "2_2") (pintype "passive"))
      (node (ref "U5") (pin "15") (pinfunction "NSLEEP_15") (pintype "input"))
    )
    (net (code "72") (name "Net-(U5-VCP)") (class "Default")
      (node (ref "C9") (pin "2") (pinfunction "2_2") (pintype "passive"))
      (node (ref "U5") (pin "9") (pinfunction "VCP_9") (pintype "bidirectional"))
    )
    (net (code "73") (name "Net-(U5-VINT)") (class "Default")
      (node (ref "C3") (pin "1") (pinfunction "1_1") (pintype "passive"))
      (node (ref "U5") (pin "12") (pinfunction "VINT_12") (pintype "power_in"))
    )
    (net (code "74") (name "Net-(U7-AISEN)") (class "Default")
      (node (ref "R19") (pin "2") (pinfunction "2_2") (pintype "passive"))
      (node (ref "U7") (pin "1") (pinfunction "AISEN_1") (pintype "bidirectional"))
    )
    (net (code "75") (name "Net-(U7-BISEN)") (class "Default")
      (node (ref "R8") (pin "2") (pinfunction "2_2") (pintype "passive"))
      (node (ref "U7") (pin "4") (pinfunction "BISEN_4") (pintype "bidirectional"))
    )
    (net (code "76") (name "Net-(U7-NSLEEP)") (class "Default")
      (node (ref "R20") (pin "2") (pinfunction "2_2") (pintype "passive"))
      (node (ref "U7") (pin "15") (pinfunction "NSLEEP_15") (pintype "input"))
    )
    (net (code "77") (name "Net-(U7-VCP)") (class "Default")
      (node (ref "C22") (pin "2") (pinfunction "2_2") (pintype "passive"))
      (node (ref "U7") (pin "9") (pinfunction "VCP_9") (pintype "bidirectional"))
    )
    (net (code "78") (name "Net-(U7-VINT)") (class "Default")
      (node (ref "C21") (pin "1") (pinfunction "1_1") (pintype "passive"))
      (node (ref "U7") (pin "12") (pinfunction "VINT_12") (pintype "power_in"))
    )
    (net (code "79") (name "Net-(U8-AISEN)") (class "Default")
      (node (ref "R21") (pin "2") (pinfunction "2_2") (pintype "passive"))
      (node (ref "U8") (pin "1") (pinfunction "AISEN_1") (pintype "bidirectional"))
    )
    (net (code "80") (name "Net-(U8-BISEN)") (class "Default")
      (node (ref "R7") (pin "2") (pinfunction "2_2") (pintype "passive"))
      (node (ref "U8") (pin "4") (pinfunction "BISEN_4") (pintype "bidirectional"))
    )
    (net (code "81") (name "Net-(U8-NSLEEP)") (class "Default")
      (node (ref "R22") (pin "2") (pinfunction "2_2") (pintype "passive"))
      (node (ref "U8") (pin "15") (pinfunction "NSLEEP_15") (pintype "input"))
    )
    (net (code "82") (name "Net-(U8-VCP)") (class "Default")
      (node (ref "C25") (pin "2") (pinfunction "2_2") (pintype "passive"))
      (node (ref "U8") (pin "9") (pinfunction "VCP_9") (pintype "bidirectional"))
    )
    (net (code "83") (name "Net-(U8-VINT)") (class "Default")
      (node (ref "C24") (pin "1") (pinfunction "1_1") (pintype "passive"))
      (node (ref "U8") (pin "12") (pinfunction "VINT_12") (pintype "power_in"))
    )
    (net (code "84") (name "VCC") (class "Default")
      (node (ref "J3") (pin "1") (pinfunction "1_1") (pintype "passive"))
      (node (ref "J4") (pin "1") (pinfunction "1_1") (pintype "passive"))
      (node (ref "J5") (pin "1") (pinfunction "1_1") (pintype "bidirectional"))
      (node (ref "ON") (pin "A") (pinfunction "A_A") (pintype "passive"))
      (node (ref "R10") (pin "1") (pinfunction "1_1") (pintype "passive"))
      (node (ref "R12") (pin "1") (pinfunction "1_1") (pintype "passive"))
      (node (ref "R14") (pin "1") (pinfunction "1_1") (pintype "passive"))
      (node (ref "R15") (pin "1") (pinfunction "1_1") (pintype "passive"))
      (node (ref "R16") (pin "1") (pinfunction "1_1") (pintype "passive"))
      (node (ref "R17") (pin "2") (pinfunction "2_2") (pintype "passive"))
      (node (ref "R2") (pin "1") (pinfunction "1_1") (pintype "passive"))
      (node (ref "R20") (pin "1") (pinfunction "1_1") (pintype "passive"))
      (node (ref "R22") (pin "1") (pinfunction "1_1") (pintype "passive"))
      (node (ref "R5") (pin "1") (pinfunction "1_1") (pintype "passive"))
      (node (ref "REG") (pin "2") (pinfunction "2_2") (pintype "passive"))
      (node (ref "U4") (pin "10") (pinfunction "VCC_2_10") (pintype "power_in"))
      (node (ref "U4") (pin "100") (pinfunction "AVCC_100") (pintype "power_in"))
      (node (ref "U4") (pin "31") (pinfunction "VCC_3_31") (pintype "power_in"))
      (node (ref "U4") (pin "61") (pinfunction "VCC_4_61") (pintype "power_in"))
      (node (ref "U4") (pin "80") (pinfunction "VCC_80") (pintype "power_in"))
    )
    (net (code "85") (name "unconnected-(U1-NFAULT-Pad6)") (class "Default")
      (node (ref "U1") (pin "6") (pinfunction "NFAULT_6") (pintype "output"))
    )
    (net (code "86") (name "unconnected-(U4-(CLKO{slash}ICP3{slash}INT7)_PE7-Pad9)") (class "Default")
      (node (ref "U4") (pin "9") (pinfunction "(CLKO/ICP3/INT7)_PE7_9") (pintype "bidirectional"))
    )
    (net (code "87") (name "unconnected-(U4-(ICP1)_PD4-Pad47)") (class "Default")
      (node (ref "U4") (pin "47") (pinfunction "(ICP1)_PD4_47") (pintype "bidirectional"))
    )
    (net (code "88") (name "unconnected-(U4-(ICP4)_PL0-Pad35)") (class "Default")
      (node (ref "U4") (pin "35") (pinfunction "(ICP4)_PL0_35") (pintype "bidirectional"))
    )
    (net (code "89") (name "unconnected-(U4-(ICP5)_PL1-Pad36)") (class "Default")
      (node (ref "U4") (pin "36") (pinfunction "(ICP5)_PL1_36") (pintype "bidirectional"))
    )
    (net (code "90") (name "unconnected-(U4-(RXD2)_PH0-Pad12)") (class "Default")
      (node (ref "U4") (pin "12") (pinfunction "(RXD2)_PH0_12") (pintype "bidirectional"))
    )
    (net (code "91") (name "unconnected-(U4-(SCL{slash}INT0)_PD0-Pad43)") (class "Default")
      (node (ref "U4") (pin "43") (pinfunction "(SCL/INT0)_PD0_43") (pintype "bidirectional"))
    )
    (net (code "92") (name "unconnected-(U4-(SDA{slash}INT1)_PD1-Pad44)") (class "Default")
      (node (ref "U4") (pin "44") (pinfunction "(SDA/INT1)_PD1_44") (pintype "bidirectional"))
    )
    (net (code "93") (name "unconnected-(U4-(SS{slash}PCINT0)_PB0-Pad19)") (class "Default")
      (node (ref "U4") (pin "19") (pinfunction "(SS/PCINT0)_PB0_19") (pintype "bidirectional"))
    )
    (net (code "94") (name "unconnected-(U4-(T0)_PD7-Pad50)") (class "Default")
      (node (ref "U4") (pin "50") (pinfunction "(T0)_PD7_50") (pintype "bidirectional"))
    )
    (net (code "95") (name "unconnected-(U4-(T1)_PD6-Pad49)") (class "Default")
      (node (ref "U4") (pin "49") (pinfunction "(T1)_PD6_49") (pintype "bidirectional"))
    )
    (net (code "96") (name "unconnected-(U4-(T3{slash}INT6)_PE6-Pad8)") (class "Default")
      (node (ref "U4") (pin "8") (pinfunction "(T3/INT6)_PE6_8") (pintype "bidirectional"))
    )
    (net (code "97") (name "unconnected-(U4-(T4)_PH7-Pad27)") (class "Default")
      (node (ref "U4") (pin "27") (pinfunction "(T4)_PH7_27") (pintype "bidirectional"))
    )
    (net (code "98") (name "unconnected-(U4-(T5)_PL2-Pad37)") (class "Default")
      (node (ref "U4") (pin "37") (pinfunction "(T5)_PL2_37") (pintype "bidirectional"))
    )
    (net (code "99") (name "unconnected-(U4-(TOSC1)_PG4-Pad29)") (class "Default")
      (node (ref "U4") (pin "29") (pinfunction "(TOSC1)_PG4_29") (pintype "bidirectional"))
    )
    (net (code "100") (name "unconnected-(U4-(TOSC2)_PG3-Pad28)") (class "Default")
      (node (ref "U4") (pin "28") (pinfunction "(TOSC2)_PG3_28") (pintype "bidirectional"))
    )
    (net (code "101") (name "unconnected-(U4-(TXD2)_PH1-Pad13)") (class "Default")
      (node (ref "U4") (pin "13") (pinfunction "(TXD2)_PH1_13") (pintype "bidirectional"))
    )
    (net (code "102") (name "unconnected-(U4-(XCK0{slash}AIN0)_PE2-Pad4)") (class "Default")
      (node (ref "U4") (pin "4") (pinfunction "(XCK0/AIN0)_PE2_4") (pintype "bidirectional"))
    )
    (net (code "103") (name "unconnected-(U4-(XCK1)_PD5-Pad48)") (class "Default")
      (node (ref "U4") (pin "48") (pinfunction "(XCK1)_PD5_48") (pintype "bidirectional"))
    )
    (net (code "104") (name "unconnected-(U4-(XCK2)_PH2-Pad14)") (class "Default")
      (node (ref "U4") (pin "14") (pinfunction "(XCK2)_PH2_14") (pintype "bidirectional"))
    )
    (net (code "105") (name "unconnected-(U4-PA5_(AD5)-Pad73)") (class "Default")
      (node (ref "U4") (pin "73") (pinfunction "PA5_(AD5)_73") (pintype "bidirectional"))
    )
    (net (code "106") (name "unconnected-(U4-PA6_(AD6)-Pad72)") (class "Default")
      (node (ref "U4") (pin "72") (pinfunction "PA6_(AD6)_72") (pintype "bidirectional"))
    )
    (net (code "107") (name "unconnected-(U4-PA7_(AD7)-Pad71)") (class "Default")
      (node (ref "U4") (pin "71") (pinfunction "PA7_(AD7)_71") (pintype "bidirectional"))
    )
    (net (code "108") (name "unconnected-(U4-PC0_(A8)-Pad53)") (class "Default")
      (node (ref "U4") (pin "53") (pinfunction "PC0_(A8)_53") (pintype "bidirectional"))
    )
    (net (code "109") (name "unconnected-(U4-PC1_(A9)-Pad54)") (class "Default")
      (node (ref "U4") (pin "54") (pinfunction "PC1_(A9)_54") (pintype "bidirectional"))
    )
    (net (code "110") (name "unconnected-(U4-PC2_(A10)-Pad55)") (class "Default")
      (node (ref "U4") (pin "55") (pinfunction "PC2_(A10)_55") (pintype "bidirectional"))
    )
    (net (code "111") (name "unconnected-(U4-PC3_(A11)-Pad56)") (class "Default")
      (node (ref "U4") (pin "56") (pinfunction "PC3_(A11)_56") (pintype "bidirectional"))
    )
    (net (code "112") (name "unconnected-(U4-PC4_(A12)-Pad57)") (class "Default")
      (node (ref "U4") (pin "57") (pinfunction "PC4_(A12)_57") (pintype "bidirectional"))
    )
    (net (code "113") (name "unconnected-(U4-PC5_(A13)-Pad58)") (class "Default")
      (node (ref "U4") (pin "58") (pinfunction "PC5_(A13)_58") (pintype "bidirectional"))
    )
    (net (code "114") (name "unconnected-(U4-PC6_(A14)-Pad59)") (class "Default")
      (node (ref "U4") (pin "59") (pinfunction "PC6_(A14)_59") (pintype "bidirectional"))
    )
    (net (code "115") (name "unconnected-(U4-PC7_(A15)-Pad60)") (class "Default")
      (node (ref "U4") (pin "60") (pinfunction "PC7_(A15)_60") (pintype "bidirectional"))
    )
    (net (code "116") (name "unconnected-(U4-PF0_(ADC0)-Pad97)") (class "Default")
      (node (ref "U4") (pin "97") (pinfunction "PF0_(ADC0)_97") (pintype "bidirectional"))
    )
    (net (code "117") (name "unconnected-(U4-PF1_(ADC1)-Pad96)") (class "Default")
      (node (ref "U4") (pin "96") (pinfunction "PF1_(ADC1)_96") (pintype "bidirectional"))
    )
    (net (code "118") (name "unconnected-(U4-PF2_(ADC2)-Pad95)") (class "Default")
      (node (ref "U4") (pin "95") (pinfunction "PF2_(ADC2)_95") (pintype "bidirectional"))
    )
    (net (code "119") (name "unconnected-(U4-PF3_(ADC3)-Pad94)") (class "Default")
      (node (ref "U4") (pin "94") (pinfunction "PF3_(ADC3)_94") (pintype "bidirectional"))
    )
    (net (code "120") (name "unconnected-(U4-PF4_(ADC4{slash}TCK)-Pad93)") (class "Default")
      (node (ref "U4") (pin "93") (pinfunction "PF4_(ADC4/TCK)_93") (pintype "bidirectional"))
    )
    (net (code "121") (name "unconnected-(U4-PF5_(ADC5{slash}TMS)-Pad92)") (class "Default")
      (node (ref "U4") (pin "92") (pinfunction "PF5_(ADC5/TMS)_92") (pintype "bidirectional"))
    )
    (net (code "122") (name "unconnected-(U4-PF7_(ADC7{slash}TDI)-Pad90)") (class "Default")
      (node (ref "U4") (pin "90") (pinfunction "PF7_(ADC7/TDI)_90") (pintype "bidirectional"))
    )
    (net (code "123") (name "unconnected-(U4-PG0_(~{WR})-Pad51)") (class "Default")
      (node (ref "U4") (pin "51") (pinfunction "PG0_(~{WR})_51") (pintype "bidirectional"))
    )
    (net (code "124") (name "unconnected-(U4-PG1_(~{RD})-Pad52)") (class "Default")
      (node (ref "U4") (pin "52") (pinfunction "PG1_(~{RD})_52") (pintype "bidirectional"))
    )
    (net (code "125") (name "unconnected-(U4-PG2_(ALE)-Pad70)") (class "Default")
      (node (ref "U4") (pin "70") (pinfunction "PG2_(ALE)_70") (pintype "bidirectional"))
    )
    (net (code "126") (name "unconnected-(U4-PJ2_(XCK3{slash}PCINT11)-Pad65)") (class "Default")
      (node (ref "U4") (pin "65") (pinfunction "PJ2_(XCK3/PCINT11)_65") (pintype "bidirectional"))
    )
    (net (code "127") (name "unconnected-(U4-PJ3_(PCINT12)-Pad66)") (class "Default")
      (node (ref "U4") (pin "66") (pinfunction "PJ3_(PCINT12)_66") (pintype "bidirectional"))
    )
    (net (code "128") (name "unconnected-(U4-PJ4_(PCINT13)-Pad67)") (class "Default")
      (node (ref "U4") (pin "67") (pinfunction "PJ4_(PCINT13)_67") (pintype "bidirectional"))
    )
    (net (code "129") (name "unconnected-(U4-PJ5_(PCINT14)-Pad68)") (class "Default")
      (node (ref "U4") (pin "68") (pinfunction "PJ5_(PCINT14)_68") (pintype "bidirectional"))
    )
    (net (code "130") (name "unconnected-(U4-PJ6_(PCINT15)-Pad69)") (class "Default")
      (node (ref "U4") (pin "69") (pinfunction "PJ6_(PCINT15)_69") (pintype "bidirectional"))
    )
    (net (code "131") (name "unconnected-(U4-PJ7-Pad79)") (class "Default")
      (node (ref "U4") (pin "79") (pinfunction "PJ7_79") (pintype "bidirectional"))
    )
    (net (code "132") (name "unconnected-(U4-PK7_(ADC15{slash}PCINT23)-Pad82)") (class "Default")
      (node (ref "U4") (pin "82") (pinfunction "PK7_(ADC15/PCINT23)_82") (pintype "bidirectional"))
    )
    (net (code "133") (name "unconnected-(U4-PL6-Pad41)") (class "Default")
      (node (ref "U4") (pin "41") (pinfunction "PL6_41") (pintype "bidirectional"))
    )
    (net (code "134") (name "unconnected-(U4-PL7-Pad42)") (class "Default")
      (node (ref "U4") (pin "42") (pinfunction "PL7_42") (pintype "bidirectional"))
    )
    (net (code "135") (name "unconnected-(U5-NFAULT-Pad6)") (class "Default")
      (node (ref "U5") (pin "6") (pinfunction "NFAULT_6") (pintype "output"))
    )
    (net (code "136") (name "unconnected-(U7-NFAULT-Pad6)") (class "Default")
      (node (ref "U7") (pin "6") (pinfunction "NFAULT_6") (pintype "output"))
    )
    (net (code "137") (name "unconnected-(U8-NFAULT-Pad6)") (class "Default")
      (node (ref "U8") (pin "6") (pinfunction "NFAULT_6") (pintype "output"))
    )
  )
)
